# untitled.net
KiCad netlist of a schematic drawn in EAGLE
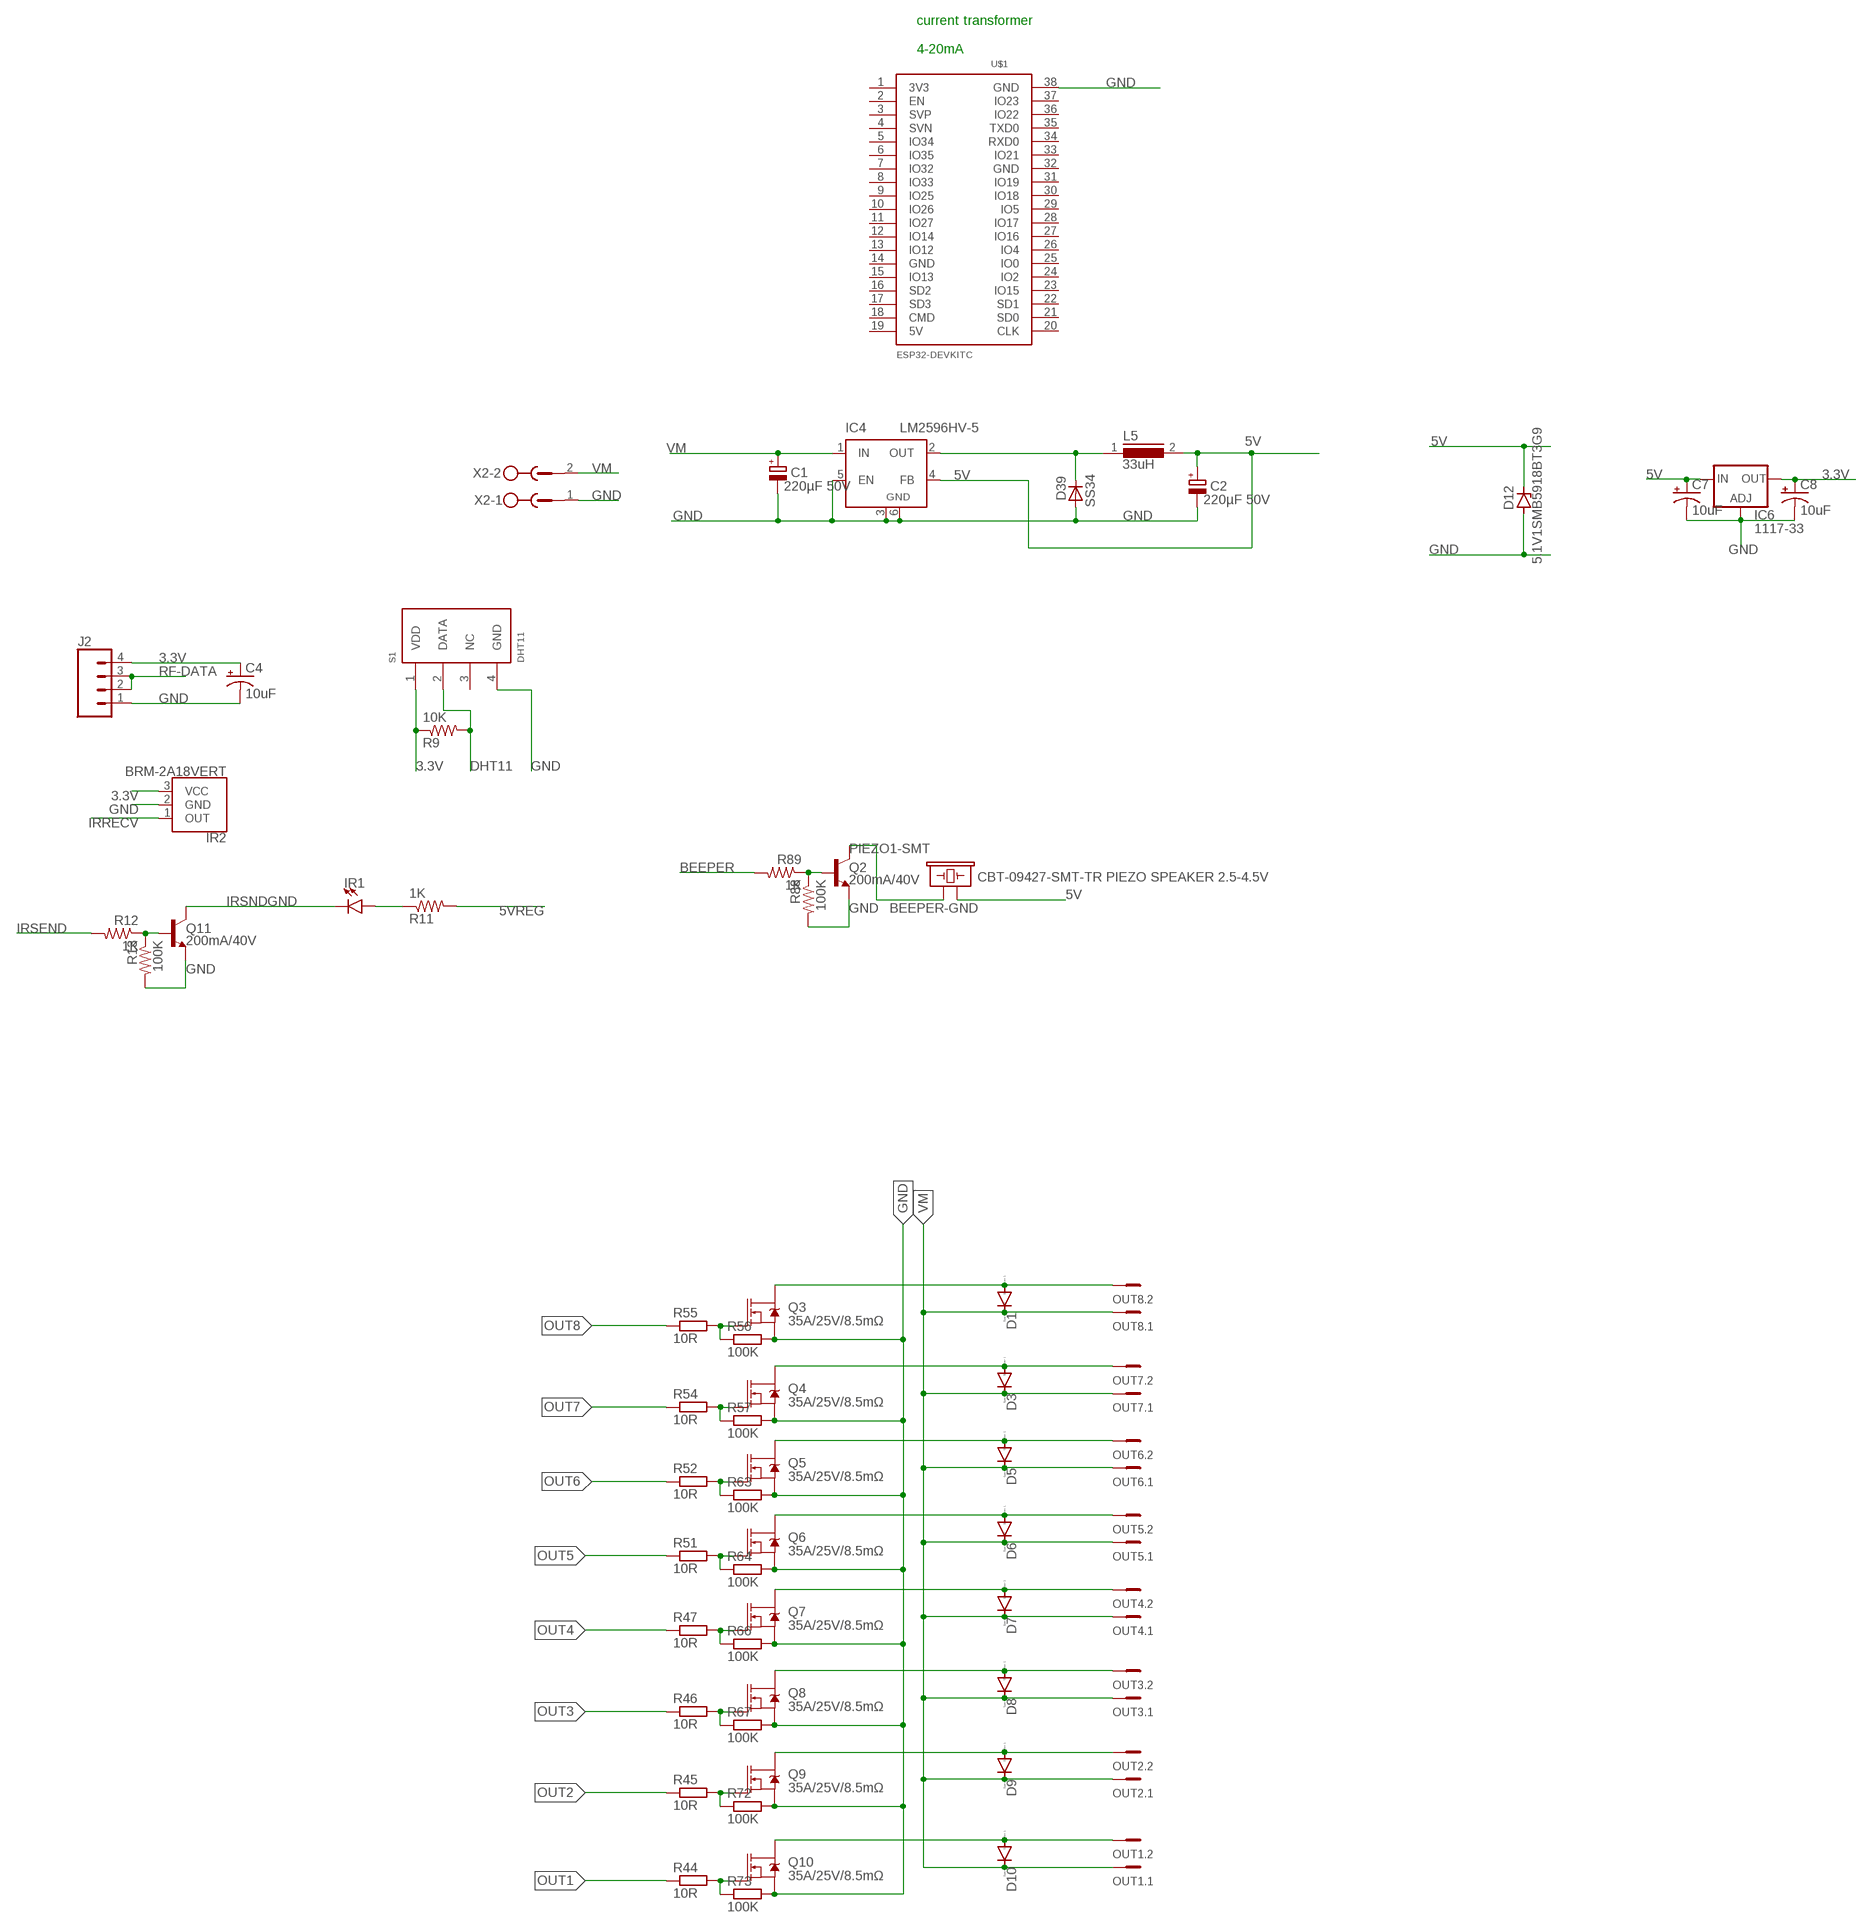
[diagram p0: schematic, sheet 1, part 1 of 2]
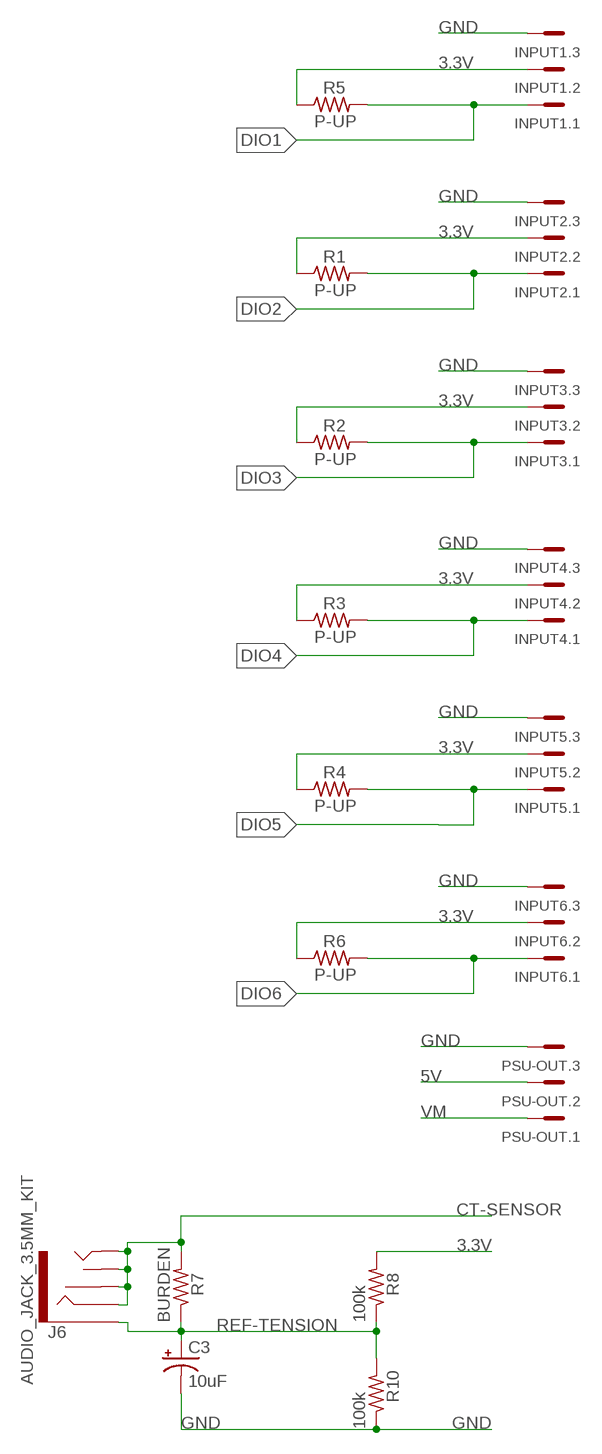
[diagram p1: schematic, sheet 1, part 2 of 2]

(export (version "E")
  (design (tool "Eeschema 10.0.6"))
  (components
    (comp (ref "C1")
      (value "220µF 50V")
      (footprint "eagle-import:E3,5-8")
      (libsource (lib "eagle-import") (part "CPOL-EUE3.5-8"))
    )
    (comp (ref "C2")
      (value "220µF 50V")
      (footprint "eagle-import:E3,5-8")
      (libsource (lib "eagle-import") (part "CPOL-EUE3.5-8"))
    )
    (comp (ref "C3")
      (value "10uF")
      (footprint "eagle-import:CPOL-RADIAL-10UF-25V")
      (libsource (lib "eagle-import") (part "CAP_POLPTH2"))
    )
    (comp (ref "C4")
      (value "10uF")
      (footprint "eagle-import:CPOL-RADIAL-10UF-25V")
      (libsource (lib "eagle-import") (part "CAP_POLPTH2"))
    )
    (comp (ref "C7")
      (value "10uF")
      (footprint "eagle-import:CPOL-RADIAL-10UF-25V")
      (libsource (lib "eagle-import") (part "CAP_POLPTH2"))
    )
    (comp (ref "C8")
      (value "10uF")
      (footprint "eagle-import:CPOL-RADIAL-10UF-25V")
      (libsource (lib "eagle-import") (part "CAP_POLPTH2"))
    )
    (comp (ref "D1")
      (value "1N4148DO35-7")
      (footprint "eagle-import:DO35-7")
      (libsource (lib "eagle-import") (part "1N4148DO35-7"))
    )
    (comp (ref "D3")
      (value "1N4148DO35-7")
      (footprint "eagle-import:DO35-7")
      (libsource (lib "eagle-import") (part "1N4148DO35-7"))
    )
    (comp (ref "D5")
      (value "1N4148DO35-7")
      (footprint "eagle-import:DO35-7")
      (libsource (lib "eagle-import") (part "1N4148DO35-7"))
    )
    (comp (ref "D6")
      (value "1N4148DO35-7")
      (footprint "eagle-import:DO35-7")
      (libsource (lib "eagle-import") (part "1N4148DO35-7"))
    )
    (comp (ref "D7")
      (value "1N4148DO35-7")
      (footprint "eagle-import:DO35-7")
      (libsource (lib "eagle-import") (part "1N4148DO35-7"))
    )
    (comp (ref "D8")
      (value "1N4148DO35-7")
      (footprint "eagle-import:DO35-7")
      (libsource (lib "eagle-import") (part "1N4148DO35-7"))
    )
    (comp (ref "D9")
      (value "1N4148DO35-7")
      (footprint "eagle-import:DO35-7")
      (libsource (lib "eagle-import") (part "1N4148DO35-7"))
    )
    (comp (ref "D10")
      (value "1N4148DO35-7")
      (footprint "eagle-import:DO35-7")
      (libsource (lib "eagle-import") (part "1N4148DO35-7"))
    )
    (comp (ref "D12")
      (value "5.1V1SMB5918BT3G9")
      (footprint "eagle-import:SMB")
      (libsource (lib "eagle-import") (part "ZENER-DIODESMB"))
    )
    (comp (ref "D39")
      (value "SS34")
      (footprint "eagle-import:SOD87")
      (libsource (lib "eagle-import") (part "D-SOD-87"))
    )
    (comp (ref "IC4")
      (value "LM2596HV-5")
      (footprint "eagle-import:TO263-5")
      (libsource (lib "eagle-import") (part "LM2596S"))
    )
    (comp (ref "IC6")
      (value "1117-33")
      (footprint "eagle-import:SOT223")
      (libsource (lib "eagle-import") (part "LD117A?S33TR"))
    )
    (comp (ref "INPUT1")
      (value "MCV3")
      (footprint "eagle-import:MCV3")
      (libsource (lib "eagle-import") (part "MCV3"))
    )
    (comp (ref "INPUT2")
      (value "MCV3")
      (footprint "eagle-import:MCV3")
      (libsource (lib "eagle-import") (part "MCV3"))
    )
    (comp (ref "INPUT3")
      (value "MCV3")
      (footprint "eagle-import:MCV3")
      (libsource (lib "eagle-import") (part "MCV3"))
    )
    (comp (ref "INPUT4")
      (value "MCV3")
      (footprint "eagle-import:MCV3")
      (libsource (lib "eagle-import") (part "MCV3"))
    )
    (comp (ref "INPUT5")
      (value "MCV3")
      (footprint "eagle-import:MCV3")
      (libsource (lib "eagle-import") (part "MCV3"))
    )
    (comp (ref "INPUT6")
      (value "MCV3")
      (footprint "eagle-import:MCV3")
      (libsource (lib "eagle-import") (part "MCV3"))
    )
    (comp (ref "IR1")
      (value "LED3MM")
      (footprint "eagle-import:LED_3MM")
      (libsource (lib "eagle-import") (part "LED3MM"))
    )
    (comp (ref "IR2")
      (value "BRM-2A18VERT")
      (footprint "eagle-import:BRM-2508_VERT")
      (libsource (lib "eagle-import") (part "BRM-2A18VERT"))
    )
    (comp (ref "J2")
      (value "CONN_04LOCK")
      (footprint "eagle-import:1X04_LOCK")
      (libsource (lib "eagle-import") (part "CONN_04LOCK"))
    )
    (comp (ref "J6")
      (value "AUDIO_JACK_3.5MM_KIT")
      (footprint "eagle-import:AUDIO-JACK-KIT")
      (libsource (lib "eagle-import") (part "AUDIO_JACK_3.5MM_KIT"))
    )
    (comp (ref "L5")
      (value "33uH")
      (footprint "eagle-import:DR127")
      (libsource (lib "eagle-import") (part "DR127"))
    )
    (comp (ref "OUT1")
      (value "MCV2")
      (footprint "eagle-import:MCV2")
      (libsource (lib "eagle-import") (part "MCV2"))
    )
    (comp (ref "OUT2")
      (value "MCV2")
      (footprint "eagle-import:MCV2")
      (libsource (lib "eagle-import") (part "MCV2"))
    )
    (comp (ref "OUT3")
      (value "MCV2")
      (footprint "eagle-import:MCV2")
      (libsource (lib "eagle-import") (part "MCV2"))
    )
    (comp (ref "OUT4")
      (value "MCV2")
      (footprint "eagle-import:MCV2")
      (libsource (lib "eagle-import") (part "MCV2"))
    )
    (comp (ref "OUT5")
      (value "MCV2")
      (footprint "eagle-import:MCV2")
      (libsource (lib "eagle-import") (part "MCV2"))
    )
    (comp (ref "OUT6")
      (value "MCV2")
      (footprint "eagle-import:MCV2")
      (libsource (lib "eagle-import") (part "MCV2"))
    )
    (comp (ref "OUT7")
      (value "MCV2")
      (footprint "eagle-import:MCV2")
      (libsource (lib "eagle-import") (part "MCV2"))
    )
    (comp (ref "OUT8")
      (value "MCV2")
      (footprint "eagle-import:MCV2")
      (libsource (lib "eagle-import") (part "MCV2"))
    )
    (comp (ref "PIEZO1-SMT")
      (value "CBT-09427-SMT-TR PIEZO SPEAKER 2.5-4.5V")
      (footprint "eagle-import:BUZZER-12MM")
      (libsource (lib "eagle-import") (part "BUZZER-PTH"))
    )
    (comp (ref "PSU-OUT")
      (value "MCV3")
      (footprint "eagle-import:MCV3")
      (libsource (lib "eagle-import") (part "MCV3"))
    )
    (comp (ref "Q2")
      (value "200mA/40V")
      (footprint "eagle-import:TO-92")
      (libsource (lib "eagle-import") (part "TRANS_NPN-2N3904"))
    )
    (comp (ref "Q3")
      (value "35A/25V/8.5mΩ")
      (footprint "eagle-import:DPAK")
      (libsource (lib "eagle-import") (part "MOSFET-NCH-FDD8780"))
    )
    (comp (ref "Q4")
      (value "35A/25V/8.5mΩ")
      (footprint "eagle-import:DPAK")
      (libsource (lib "eagle-import") (part "MOSFET-NCH-FDD8780"))
    )
    (comp (ref "Q5")
      (value "35A/25V/8.5mΩ")
      (footprint "eagle-import:DPAK")
      (libsource (lib "eagle-import") (part "MOSFET-NCH-FDD8780"))
    )
    (comp (ref "Q6")
      (value "35A/25V/8.5mΩ")
      (footprint "eagle-import:DPAK")
      (libsource (lib "eagle-import") (part "MOSFET-NCH-FDD8780"))
    )
    (comp (ref "Q7")
      (value "35A/25V/8.5mΩ")
      (footprint "eagle-import:DPAK")
      (libsource (lib "eagle-import") (part "MOSFET-NCH-FDD8780"))
    )
    (comp (ref "Q8")
      (value "35A/25V/8.5mΩ")
      (footprint "eagle-import:DPAK")
      (libsource (lib "eagle-import") (part "MOSFET-NCH-FDD8780"))
    )
    (comp (ref "Q9")
      (value "35A/25V/8.5mΩ")
      (footprint "eagle-import:DPAK")
      (libsource (lib "eagle-import") (part "MOSFET-NCH-FDD8780"))
    )
    (comp (ref "Q10")
      (value "35A/25V/8.5mΩ")
      (footprint "eagle-import:DPAK")
      (libsource (lib "eagle-import") (part "MOSFET-NCH-FDD8780"))
    )
    (comp (ref "Q11")
      (value "200mA/40V")
      (footprint "eagle-import:TO-92")
      (libsource (lib "eagle-import") (part "TRANS_NPN-2N3904"))
    )
    (comp (ref "R1")
      (value "P-UP")
      (footprint "eagle-import:0204_7")
      (libsource (lib "eagle-import") (part "resistor_R-US_0204/7"))
    )
    (comp (ref "R2")
      (value "P-UP")
      (footprint "eagle-import:0204_7")
      (libsource (lib "eagle-import") (part "resistor_R-US_0204/7"))
    )
    (comp (ref "R3")
      (value "P-UP")
      (footprint "eagle-import:0204_7")
      (libsource (lib "eagle-import") (part "resistor_R-US_0204/7"))
    )
    (comp (ref "R4")
      (value "P-UP")
      (footprint "eagle-import:0204_7")
      (libsource (lib "eagle-import") (part "resistor_R-US_0204/7"))
    )
    (comp (ref "R5")
      (value "P-UP")
      (footprint "eagle-import:0204_7")
      (libsource (lib "eagle-import") (part "resistor_R-US_0204/7"))
    )
    (comp (ref "R6")
      (value "P-UP")
      (footprint "eagle-import:0204_7")
      (libsource (lib "eagle-import") (part "resistor_R-US_0204/7"))
    )
    (comp (ref "R7")
      (value "BURDEN")
      (footprint "eagle-import:0204_7")
      (libsource (lib "eagle-import") (part "resistor_R-US_0204/7"))
    )
    (comp (ref "R8")
      (value "100k")
      (footprint "eagle-import:0204_7")
      (libsource (lib "eagle-import") (part "resistor_R-US_0204/7"))
    )
    (comp (ref "R9")
      (value "10K")
      (footprint "eagle-import:0204_7")
      (libsource (lib "eagle-import") (part "R-US_0204/7"))
    )
    (comp (ref "R10")
      (value "100k")
      (footprint "eagle-import:0204_7")
      (libsource (lib "eagle-import") (part "resistor_R-US_0204/7"))
    )
    (comp (ref "R11")
      (value "1K")
      (footprint "eagle-import:0204_7")
      (libsource (lib "eagle-import") (part "R-US_0204/7"))
    )
    (comp (ref "R12")
      (value "1K")
      (footprint "eagle-import:0204_7")
      (libsource (lib "eagle-import") (part "adafruit_420_R-US_0204/7"))
    )
    (comp (ref "R13")
      (value "100K")
      (footprint "eagle-import:0204_7")
      (libsource (lib "eagle-import") (part "adafruit_420_R-US_0204/7"))
    )
    (comp (ref "R44")
      (value "10R")
      (footprint "eagle-import:0204_7")
      (libsource (lib "eagle-import") (part "R-EU_0204/7"))
    )
    (comp (ref "R45")
      (value "10R")
      (footprint "eagle-import:0204_7")
      (libsource (lib "eagle-import") (part "R-EU_0204/7"))
    )
    (comp (ref "R46")
      (value "10R")
      (footprint "eagle-import:0204_7")
      (libsource (lib "eagle-import") (part "R-EU_0204/7"))
    )
    (comp (ref "R47")
      (value "10R")
      (footprint "eagle-import:0204_7")
      (libsource (lib "eagle-import") (part "R-EU_0204/7"))
    )
    (comp (ref "R51")
      (value "10R")
      (footprint "eagle-import:0204_7")
      (libsource (lib "eagle-import") (part "R-EU_0204/7"))
    )
    (comp (ref "R52")
      (value "10R")
      (footprint "eagle-import:0204_7")
      (libsource (lib "eagle-import") (part "R-EU_0204/7"))
    )
    (comp (ref "R54")
      (value "10R")
      (footprint "eagle-import:0204_7")
      (libsource (lib "eagle-import") (part "R-EU_0204/7"))
    )
    (comp (ref "R55")
      (value "10R")
      (footprint "eagle-import:0204_7")
      (libsource (lib "eagle-import") (part "R-EU_0204/7"))
    )
    (comp (ref "R56")
      (value "100K")
      (footprint "eagle-import:0204_7")
      (libsource (lib "eagle-import") (part "R-EU_0204/7"))
    )
    (comp (ref "R57")
      (value "100K")
      (footprint "eagle-import:0204_7")
      (libsource (lib "eagle-import") (part "R-EU_0204/7"))
    )
    (comp (ref "R63")
      (value "100K")
      (footprint "eagle-import:0204_7")
      (libsource (lib "eagle-import") (part "R-EU_0204/7"))
    )
    (comp (ref "R64")
      (value "100K")
      (footprint "eagle-import:0204_7")
      (libsource (lib "eagle-import") (part "R-EU_0204/7"))
    )
    (comp (ref "R66")
      (value "100K")
      (footprint "eagle-import:0204_7")
      (libsource (lib "eagle-import") (part "R-EU_0204/7"))
    )
    (comp (ref "R67")
      (value "100K")
      (footprint "eagle-import:0204_7")
      (libsource (lib "eagle-import") (part "R-EU_0204/7"))
    )
    (comp (ref "R72")
      (value "100K")
      (footprint "eagle-import:0204_7")
      (libsource (lib "eagle-import") (part "R-EU_0204/7"))
    )
    (comp (ref "R73")
      (value "100K")
      (footprint "eagle-import:0204_7")
      (libsource (lib "eagle-import") (part "R-EU_0204/7"))
    )
    (comp (ref "R88")
      (value "100K")
      (footprint "eagle-import:0204_7")
      (libsource (lib "eagle-import") (part "adafruit_420_R-US_0204/7"))
    )
    (comp (ref "R89")
      (value "1K")
      (footprint "eagle-import:0204_7")
      (libsource (lib "eagle-import") (part "adafruit_420_R-US_0204/7"))
    )
    (comp (ref "S1")
      (value "DHT11")
      (footprint "eagle-import:DHT11")
      (libsource (lib "eagle-import") (part "DHT11"))
    )
    (comp (ref "U$1")
      (value "ESP32NODEMCU")
      (footprint "eagle-import:ESP32NODEMCU")
      (libsource (lib "eagle-import") (part "ESP32NODEMCU"))
    )
    (comp (ref "X2")
      (value "MSTBV2")
      (footprint "eagle-import:MSTBV2")
      (libsource (lib "eagle-import") (part "MSTBV2"))
    )
  )
  (nets
    (net (code "1") (name "/3.3V") (class "Default")
      (node (ref "C4") (pin "1") (pinfunction "+_1") (pintype "passive"))
      (node (ref "C8") (pin "1") (pinfunction "+_1") (pintype "passive"))
      (node (ref "IC6") (pin "4") (pinfunction "OUT_4") (pintype "passive"))
      (node (ref "INPUT1") (pin "2") (pinfunction "SK_2") (pintype "passive"))
      (node (ref "INPUT2") (pin "2") (pinfunction "SK_2") (pintype "passive"))
      (node (ref "INPUT3") (pin "2") (pinfunction "SK_2") (pintype "passive"))
      (node (ref "INPUT4") (pin "2") (pinfunction "SK_2") (pintype "passive"))
      (node (ref "INPUT5") (pin "2") (pinfunction "SK_2") (pintype "passive"))
      (node (ref "INPUT6") (pin "2") (pinfunction "SK_2") (pintype "passive"))
      (node (ref "IR2") (pin "3") (pinfunction "VCC_3") (pintype "bidirectional"))
      (node (ref "J2") (pin "4") (pinfunction "4_4") (pintype "passive"))
      (node (ref "R1") (pin "1") (pinfunction "1_1") (pintype "passive"))
      (node (ref "R2") (pin "1") (pinfunction "1_1") (pintype "passive"))
      (node (ref "R3") (pin "1") (pinfunction "1_1") (pintype "passive"))
      (node (ref "R4") (pin "1") (pinfunction "1_1") (pintype "passive"))
      (node (ref "R5") (pin "1") (pinfunction "1_1") (pintype "passive"))
      (node (ref "R6") (pin "1") (pinfunction "1_1") (pintype "passive"))
      (node (ref "R8") (pin "2") (pinfunction "2_2") (pintype "passive"))
      (node (ref "R9") (pin "1") (pinfunction "1_1") (pintype "passive"))
      (node (ref "S1") (pin "1") (pinfunction "VDD_1") (pintype "power_in"))
    )
    (net (code "2") (name "/5V") (class "Default")
      (node (ref "C2") (pin "+") (pinfunction "+_+") (pintype "passive"))
      (node (ref "C7") (pin "1") (pinfunction "+_1") (pintype "passive"))
      (node (ref "D12") (pin "C") (pinfunction "C_C") (pintype "passive"))
      (node (ref "IC4") (pin "4") (pinfunction "FB_4") (pintype "input"))
      (node (ref "IC6") (pin "3") (pinfunction "IN_3") (pintype "input"))
      (node (ref "L5") (pin "2") (pinfunction "2_2") (pintype "passive"))
      (node (ref "PIEZO1-SMT") (pin "+") (pinfunction "1_+") (pintype "passive"))
      (node (ref "PSU-OUT") (pin "2") (pinfunction "SK_2") (pintype "passive"))
    )
    (net (code "3") (name "/5VREG") (class "Default")
      (node (ref "R11") (pin "2") (pinfunction "2_2") (pintype "passive"))
    )
    (net (code "4") (name "/BEEPER") (class "Default")
      (node (ref "R89") (pin "2") (pinfunction "2_2") (pintype "passive"))
    )
    (net (code "5") (name "/BEEPER-GND") (class "Default")
      (node (ref "PIEZO1-SMT") (pin "-") (pinfunction "2_-") (pintype "passive"))
      (node (ref "Q2") (pin "3") (pinfunction "C_3") (pintype "passive"))
    )
    (net (code "6") (name "/CT-SENSOR") (class "Default")
      (node (ref "J6") (pin "RING") (pinfunction "RING_RING") (pintype "bidirectional"))
      (node (ref "J6") (pin "RSH") (pinfunction "RSH_RSH") (pintype "bidirectional"))
      (node (ref "J6") (pin "TIP") (pinfunction "TIP_TIP") (pintype "bidirectional"))
      (node (ref "J6") (pin "TSH") (pinfunction "TSH_TSH") (pintype "bidirectional"))
      (node (ref "R7") (pin "2") (pinfunction "2_2") (pintype "passive"))
    )
    (net (code "7") (name "/DHT11") (class "Default")
      (node (ref "R9") (pin "2") (pinfunction "2_2") (pintype "passive"))
      (node (ref "S1") (pin "2") (pinfunction "DATA_2") (pintype "bidirectional"))
    )
    (net (code "8") (name "/IRRECV") (class "Default")
      (node (ref "IR2") (pin "1") (pinfunction "OUT_1") (pintype "bidirectional"))
    )
    (net (code "9") (name "/IRSEND") (class "Default")
      (node (ref "R12") (pin "2") (pinfunction "2_2") (pintype "passive"))
    )
    (net (code "10") (name "/IRSNDGND") (class "Default")
      (node (ref "IR1") (pin "K") (pinfunction "C_K") (pintype "passive"))
      (node (ref "Q11") (pin "3") (pinfunction "C_3") (pintype "passive"))
    )
    (net (code "11") (name "/REF-TENSION") (class "Default")
      (node (ref "C3") (pin "1") (pinfunction "+_1") (pintype "passive"))
      (node (ref "J6") (pin "SLEEVE") (pinfunction "SLEEVE_SLEEVE") (pintype "bidirectional"))
      (node (ref "R10") (pin "2") (pinfunction "2_2") (pintype "passive"))
      (node (ref "R7") (pin "1") (pinfunction "1_1") (pintype "passive"))
      (node (ref "R8") (pin "1") (pinfunction "1_1") (pintype "passive"))
    )
    (net (code "12") (name "/RF-DATA") (class "Default")
      (node (ref "J2") (pin "2") (pinfunction "2_2") (pintype "passive"))
      (node (ref "J2") (pin "3") (pinfunction "3_3") (pintype "passive"))
    )
    (net (code "13") (name "DIO1") (class "Default")
      (node (ref "INPUT1") (pin "1") (pinfunction "SK_1") (pintype "passive"))
      (node (ref "R5") (pin "2") (pinfunction "2_2") (pintype "passive"))
    )
    (net (code "14") (name "DIO2") (class "Default")
      (node (ref "INPUT2") (pin "1") (pinfunction "SK_1") (pintype "passive"))
      (node (ref "R1") (pin "2") (pinfunction "2_2") (pintype "passive"))
    )
    (net (code "15") (name "DIO3") (class "Default")
      (node (ref "INPUT3") (pin "1") (pinfunction "SK_1") (pintype "passive"))
      (node (ref "R2") (pin "2") (pinfunction "2_2") (pintype "passive"))
    )
    (net (code "16") (name "DIO4") (class "Default")
      (node (ref "INPUT4") (pin "1") (pinfunction "SK_1") (pintype "passive"))
      (node (ref "R3") (pin "2") (pinfunction "2_2") (pintype "passive"))
    )
    (net (code "17") (name "DIO5") (class "Default")
      (node (ref "INPUT5") (pin "1") (pinfunction "SK_1") (pintype "passive"))
      (node (ref "R4") (pin "2") (pinfunction "2_2") (pintype "passive"))
    )
    (net (code "18") (name "DIO6") (class "Default")
      (node (ref "INPUT6") (pin "1") (pinfunction "SK_1") (pintype "passive"))
      (node (ref "R6") (pin "2") (pinfunction "2_2") (pintype "passive"))
    )
    (net (code "19") (name "GND") (class "Default")
      (node (ref "C1") (pin "-") (pinfunction "-_-") (pintype "passive"))
      (node (ref "C2") (pin "-") (pinfunction "-_-") (pintype "passive"))
      (node (ref "C3") (pin "2") (pinfunction "-_2") (pintype "passive"))
      (node (ref "C4") (pin "2") (pinfunction "-_2") (pintype "passive"))
      (node (ref "C7") (pin "2") (pinfunction "-_2") (pintype "passive"))
      (node (ref "C8") (pin "2") (pinfunction "-_2") (pintype "passive"))
      (node (ref "D12") (pin "A") (pinfunction "A_A") (pintype "passive"))
      (node (ref "D39") (pin "2") (pinfunction "A_2") (pintype "passive"))
      (node (ref "IC4") (pin "3") (pinfunction "GND_3") (pintype "power_in"))
      (node (ref "IC4") (pin "5") (pinfunction "EN_5") (pintype "input"))
      (node (ref "IC4") (pin "6") (pinfunction "GND_6") (pintype "power_in"))
      (node (ref "IC6") (pin "1") (pinfunction "ADJ_1") (pintype "input"))
      (node (ref "INPUT1") (pin "3") (pinfunction "SK_3") (pintype "passive"))
      (node (ref "INPUT2") (pin "3") (pinfunction "SK_3") (pintype "passive"))
      (node (ref "INPUT3") (pin "3") (pinfunction "SK_3") (pintype "passive"))
      (node (ref "INPUT4") (pin "3") (pinfunction "SK_3") (pintype "passive"))
      (node (ref "INPUT5") (pin "3") (pinfunction "SK_3") (pintype "passive"))
      (node (ref "INPUT6") (pin "3") (pinfunction "SK_3") (pintype "passive"))
      (node (ref "IR2") (pin "2") (pinfunction "GND_2") (pintype "bidirectional"))
      (node (ref "J2") (pin "1") (pinfunction "1_1") (pintype "passive"))
      (node (ref "PSU-OUT") (pin "3") (pinfunction "SK_3") (pintype "passive"))
      (node (ref "Q10") (pin "3") (pinfunction "S_3") (pintype "bidirectional"))
      (node (ref "Q11") (pin "1") (pinfunction "E_1") (pintype "passive"))
      (node (ref "Q2") (pin "1") (pinfunction "E_1") (pintype "passive"))
      (node (ref "Q3") (pin "3") (pinfunction "S_3") (pintype "bidirectional"))
      (node (ref "Q4") (pin "3") (pinfunction "S_3") (pintype "bidirectional"))
      (node (ref "Q5") (pin "3") (pinfunction "S_3") (pintype "bidirectional"))
      (node (ref "Q6") (pin "3") (pinfunction "S_3") (pintype "bidirectional"))
      (node (ref "Q7") (pin "3") (pinfunction "S_3") (pintype "bidirectional"))
      (node (ref "Q8") (pin "3") (pinfunction "S_3") (pintype "bidirectional"))
      (node (ref "Q9") (pin "3") (pinfunction "S_3") (pintype "bidirectional"))
      (node (ref "R10") (pin "1") (pinfunction "1_1") (pintype "passive"))
      (node (ref "R13") (pin "2") (pinfunction "2_2") (pintype "passive"))
      (node (ref "R56") (pin "2") (pinfunction "2_2") (pintype "passive"))
      (node (ref "R57") (pin "2") (pinfunction "2_2") (pintype "passive"))
      (node (ref "R63") (pin "2") (pinfunction "2_2") (pintype "passive"))
      (node (ref "R64") (pin "2") (pinfunction "2_2") (pintype "passive"))
      (node (ref "R66") (pin "2") (pinfunction "2_2") (pintype "passive"))
      (node (ref "R67") (pin "2") (pinfunction "2_2") (pintype "passive"))
      (node (ref "R72") (pin "2") (pinfunction "2_2") (pintype "passive"))
      (node (ref "R73") (pin "2") (pinfunction "2_2") (pintype "passive"))
      (node (ref "R88") (pin "2") (pinfunction "2_2") (pintype "passive"))
      (node (ref "S1") (pin "4") (pinfunction "GND_4") (pintype "power_in"))
      (node (ref "U$1") (pin "38") (pinfunction "GND_38") (pintype "bidirectional"))
      (node (ref "X2") (pin "1") (pinfunction "SK_1") (pintype "passive"))
    )
    (net (code "20") (name "Net-(D39-C)") (class "Default")
      (node (ref "D39") (pin "1") (pinfunction "C_1") (pintype "passive"))
      (node (ref "IC4") (pin "2") (pinfunction "OUT_2") (pintype "output"))
      (node (ref "L5") (pin "1") (pinfunction "1_1") (pintype "passive"))
    )
    (net (code "21") (name "Net-(IR1-PadA)") (class "Default")
      (node (ref "IR1") (pin "A") (pinfunction "A_A") (pintype "passive"))
      (node (ref "R11") (pin "1") (pinfunction "1_1") (pintype "passive"))
    )
    (net (code "22") (name "Net-(OUT1B-SK)") (class "Default")
      (node (ref "D10") (pin "A") (pinfunction "A_A") (pintype "passive"))
      (node (ref "OUT1") (pin "2") (pinfunction "SK_2") (pintype "passive"))
      (node (ref "Q10") (pin "4") (pinfunction "D_4") (pintype "bidirectional"))
    )
    (net (code "23") (name "Net-(OUT2B-SK)") (class "Default")
      (node (ref "D9") (pin "A") (pinfunction "A_A") (pintype "passive"))
      (node (ref "OUT2") (pin "2") (pinfunction "SK_2") (pintype "passive"))
      (node (ref "Q9") (pin "4") (pinfunction "D_4") (pintype "bidirectional"))
    )
    (net (code "24") (name "Net-(OUT3B-SK)") (class "Default")
      (node (ref "D8") (pin "A") (pinfunction "A_A") (pintype "passive"))
      (node (ref "OUT3") (pin "2") (pinfunction "SK_2") (pintype "passive"))
      (node (ref "Q8") (pin "4") (pinfunction "D_4") (pintype "bidirectional"))
    )
    (net (code "25") (name "Net-(OUT4B-SK)") (class "Default")
      (node (ref "D7") (pin "A") (pinfunction "A_A") (pintype "passive"))
      (node (ref "OUT4") (pin "2") (pinfunction "SK_2") (pintype "passive"))
      (node (ref "Q7") (pin "4") (pinfunction "D_4") (pintype "bidirectional"))
    )
    (net (code "26") (name "Net-(OUT5B-SK)") (class "Default")
      (node (ref "D6") (pin "A") (pinfunction "A_A") (pintype "passive"))
      (node (ref "OUT5") (pin "2") (pinfunction "SK_2") (pintype "passive"))
      (node (ref "Q6") (pin "4") (pinfunction "D_4") (pintype "bidirectional"))
    )
    (net (code "27") (name "Net-(OUT6B-SK)") (class "Default")
      (node (ref "D5") (pin "A") (pinfunction "A_A") (pintype "passive"))
      (node (ref "OUT6") (pin "2") (pinfunction "SK_2") (pintype "passive"))
      (node (ref "Q5") (pin "4") (pinfunction "D_4") (pintype "bidirectional"))
    )
    (net (code "28") (name "Net-(OUT7B-SK)") (class "Default")
      (node (ref "D3") (pin "A") (pinfunction "A_A") (pintype "passive"))
      (node (ref "OUT7") (pin "2") (pinfunction "SK_2") (pintype "passive"))
      (node (ref "Q4") (pin "4") (pinfunction "D_4") (pintype "bidirectional"))
    )
    (net (code "29") (name "Net-(OUT8B-SK)") (class "Default")
      (node (ref "D1") (pin "A") (pinfunction "A_A") (pintype "passive"))
      (node (ref "OUT8") (pin "2") (pinfunction "SK_2") (pintype "passive"))
      (node (ref "Q3") (pin "4") (pinfunction "D_4") (pintype "bidirectional"))
    )
    (net (code "30") (name "Net-(Q2-B)") (class "Default")
      (node (ref "Q2") (pin "2") (pinfunction "B_2") (pintype "passive"))
      (node (ref "R88") (pin "1") (pinfunction "1_1") (pintype "passive"))
      (node (ref "R89") (pin "1") (pinfunction "1_1") (pintype "passive"))
    )
    (net (code "31") (name "Net-(Q3-G)") (class "Default")
      (node (ref "Q3") (pin "1") (pinfunction "G_1") (pintype "bidirectional"))
      (node (ref "R55") (pin "2") (pinfunction "2_2") (pintype "passive"))
      (node (ref "R56") (pin "1") (pinfunction "1_1") (pintype "passive"))
    )
    (net (code "32") (name "Net-(Q4-G)") (class "Default")
      (node (ref "Q4") (pin "1") (pinfunction "G_1") (pintype "bidirectional"))
      (node (ref "R54") (pin "2") (pinfunction "2_2") (pintype "passive"))
      (node (ref "R57") (pin "1") (pinfunction "1_1") (pintype "passive"))
    )
    (net (code "33") (name "Net-(Q5-G)") (class "Default")
      (node (ref "Q5") (pin "1") (pinfunction "G_1") (pintype "bidirectional"))
      (node (ref "R52") (pin "2") (pinfunction "2_2") (pintype "passive"))
      (node (ref "R63") (pin "1") (pinfunction "1_1") (pintype "passive"))
    )
    (net (code "34") (name "Net-(Q6-G)") (class "Default")
      (node (ref "Q6") (pin "1") (pinfunction "G_1") (pintype "bidirectional"))
      (node (ref "R51") (pin "2") (pinfunction "2_2") (pintype "passive"))
      (node (ref "R64") (pin "1") (pinfunction "1_1") (pintype "passive"))
    )
    (net (code "35") (name "Net-(Q7-G)") (class "Default")
      (node (ref "Q7") (pin "1") (pinfunction "G_1") (pintype "bidirectional"))
      (node (ref "R47") (pin "2") (pinfunction "2_2") (pintype "passive"))
      (node (ref "R66") (pin "1") (pinfunction "1_1") (pintype "passive"))
    )
    (net (code "36") (name "Net-(Q8-G)") (class "Default")
      (node (ref "Q8") (pin "1") (pinfunction "G_1") (pintype "bidirectional"))
      (node (ref "R46") (pin "2") (pinfunction "2_2") (pintype "passive"))
      (node (ref "R67") (pin "1") (pinfunction "1_1") (pintype "passive"))
    )
    (net (code "37") (name "Net-(Q9-G)") (class "Default")
      (node (ref "Q9") (pin "1") (pinfunction "G_1") (pintype "bidirectional"))
      (node (ref "R45") (pin "2") (pinfunction "2_2") (pintype "passive"))
      (node (ref "R72") (pin "1") (pinfunction "1_1") (pintype "passive"))
    )
    (net (code "38") (name "Net-(Q10-G)") (class "Default")
      (node (ref "Q10") (pin "1") (pinfunction "G_1") (pintype "bidirectional"))
      (node (ref "R44") (pin "2") (pinfunction "2_2") (pintype "passive"))
      (node (ref "R73") (pin "1") (pinfunction "1_1") (pintype "passive"))
    )
    (net (code "39") (name "Net-(Q11-B)") (class "Default")
      (node (ref "Q11") (pin "2") (pinfunction "B_2") (pintype "passive"))
      (node (ref "R12") (pin "1") (pinfunction "1_1") (pintype "passive"))
      (node (ref "R13") (pin "1") (pinfunction "1_1") (pintype "passive"))
    )
    (net (code "40") (name "OUT1") (class "Default")
      (node (ref "R44") (pin "1") (pinfunction "1_1") (pintype "passive"))
    )
    (net (code "41") (name "OUT2") (class "Default")
      (node (ref "R45") (pin "1") (pinfunction "1_1") (pintype "passive"))
    )
    (net (code "42") (name "OUT3") (class "Default")
      (node (ref "R46") (pin "1") (pinfunction "1_1") (pintype "passive"))
    )
    (net (code "43") (name "OUT4") (class "Default")
      (node (ref "R47") (pin "1") (pinfunction "1_1") (pintype "passive"))
    )
    (net (code "44") (name "OUT5") (class "Default")
      (node (ref "R51") (pin "1") (pinfunction "1_1") (pintype "passive"))
    )
    (net (code "45") (name "OUT6") (class "Default")
      (node (ref "R52") (pin "1") (pinfunction "1_1") (pintype "passive"))
    )
    (net (code "46") (name "OUT7") (class "Default")
      (node (ref "R54") (pin "1") (pinfunction "1_1") (pintype "passive"))
    )
    (net (code "47") (name "OUT8") (class "Default")
      (node (ref "R55") (pin "1") (pinfunction "1_1") (pintype "passive"))
    )
    (net (code "48") (name "VM") (class "Default")
      (node (ref "C1") (pin "+") (pinfunction "+_+") (pintype "passive"))
      (node (ref "D1") (pin "C") (pinfunction "C_C") (pintype "passive"))
      (node (ref "D10") (pin "C") (pinfunction "C_C") (pintype "passive"))
      (node (ref "D3") (pin "C") (pinfunction "C_C") (pintype "passive"))
      (node (ref "D5") (pin "C") (pinfunction "C_C") (pintype "passive"))
      (node (ref "D6") (pin "C") (pinfunction "C_C") (pintype "passive"))
      (node (ref "D7") (pin "C") (pinfunction "C_C") (pintype "passive"))
      (node (ref "D8") (pin "C") (pinfunction "C_C") (pintype "passive"))
      (node (ref "D9") (pin "C") (pinfunction "C_C") (pintype "passive"))
      (node (ref "IC4") (pin "1") (pinfunction "IN_1") (pintype "input"))
      (node (ref "OUT1") (pin "1") (pinfunction "SK_1") (pintype "passive"))
      (node (ref "OUT2") (pin "1") (pinfunction "SK_1") (pintype "passive"))
      (node (ref "OUT3") (pin "1") (pinfunction "SK_1") (pintype "passive"))
      (node (ref "OUT4") (pin "1") (pinfunction "SK_1") (pintype "passive"))
      (node (ref "OUT5") (pin "1") (pinfunction "SK_1") (pintype "passive"))
      (node (ref "OUT6") (pin "1") (pinfunction "SK_1") (pintype "passive"))
      (node (ref "OUT7") (pin "1") (pinfunction "SK_1") (pintype "passive"))
      (node (ref "OUT8") (pin "1") (pinfunction "SK_1") (pintype "passive"))
      (node (ref "PSU-OUT") (pin "1") (pinfunction "SK_1") (pintype "passive"))
      (node (ref "X2") (pin "2") (pinfunction "SK_2") (pintype "passive"))
    )
    (net (code "49") (name "unconnected-(S1-NC-Pad3)") (class "Default")
      (node (ref "S1") (pin "3") (pinfunction "NC_3") (pintype "bidirectional"))
    )
    (net (code "50") (name "unconnected-(U$1-3V3-Pad1)") (class "Default")
      (node (ref "U$1") (pin "1") (pinfunction "3V3_1") (pintype "bidirectional"))
    )
    (net (code "51") (name "unconnected-(U$1-5V-Pad19)") (class "Default")
      (node (ref "U$1") (pin "19") (pinfunction "5V_19") (pintype "bidirectional"))
    )
    (net (code "52") (name "unconnected-(U$1-CLK-Pad20)") (class "Default")
      (node (ref "U$1") (pin "20") (pinfunction "CLK_20") (pintype "bidirectional"))
    )
    (net (code "53") (name "unconnected-(U$1-CMD-Pad18)") (class "Default")
      (node (ref "U$1") (pin "18") (pinfunction "CMD_18") (pintype "bidirectional"))
    )
    (net (code "54") (name "unconnected-(U$1-EN-Pad2)") (class "Default")
      (node (ref "U$1") (pin "2") (pinfunction "EN_2") (pintype "bidirectional"))
    )
    (net (code "55") (name "unconnected-(U$1-GND-Pad14)") (class "Default")
      (node (ref "U$1") (pin "14") (pinfunction "GND_14") (pintype "bidirectional"))
    )
    (net (code "56") (name "unconnected-(U$1-GND-Pad32)") (class "Default")
      (node (ref "U$1") (pin "32") (pinfunction "GND_32") (pintype "bidirectional"))
    )
    (net (code "57") (name "unconnected-(U$1-IO0-Pad25)") (class "Default")
      (node (ref "U$1") (pin "25") (pinfunction "IO0_25") (pintype "bidirectional"))
    )
    (net (code "58") (name "unconnected-(U$1-IO2-Pad24)") (class "Default")
      (node (ref "U$1") (pin "24") (pinfunction "IO2_24") (pintype "bidirectional"))
    )
    (net (code "59") (name "unconnected-(U$1-IO4-Pad26)") (class "Default")
      (node (ref "U$1") (pin "26") (pinfunction "IO4_26") (pintype "bidirectional"))
    )
    (net (code "60") (name "unconnected-(U$1-IO5-Pad29)") (class "Default")
      (node (ref "U$1") (pin "29") (pinfunction "IO5_29") (pintype "bidirectional"))
    )
    (net (code "61") (name "unconnected-(U$1-IO12-Pad13)") (class "Default")
      (node (ref "U$1") (pin "13") (pinfunction "IO12_13") (pintype "bidirectional"))
    )
    (net (code "62") (name "unconnected-(U$1-IO13-Pad15)") (class "Default")
      (node (ref "U$1") (pin "15") (pinfunction "IO13_15") (pintype "bidirectional"))
    )
    (net (code "63") (name "unconnected-(U$1-IO14-Pad12)") (class "Default")
      (node (ref "U$1") (pin "12") (pinfunction "IO14_12") (pintype "bidirectional"))
    )
    (net (code "64") (name "unconnected-(U$1-IO15-Pad23)") (class "Default")
      (node (ref "U$1") (pin "23") (pinfunction "IO15_23") (pintype "bidirectional"))
    )
    (net (code "65") (name "unconnected-(U$1-IO16-Pad27)") (class "Default")
      (node (ref "U$1") (pin "27") (pinfunction "IO16_27") (pintype "bidirectional"))
    )
    (net (code "66") (name "unconnected-(U$1-IO17-Pad28)") (class "Default")
      (node (ref "U$1") (pin "28") (pinfunction "IO17_28") (pintype "bidirectional"))
    )
    (net (code "67") (name "unconnected-(U$1-IO18-Pad30)") (class "Default")
      (node (ref "U$1") (pin "30") (pinfunction "IO18_30") (pintype "bidirectional"))
    )
    (net (code "68") (name "unconnected-(U$1-IO19-Pad31)") (class "Default")
      (node (ref "U$1") (pin "31") (pinfunction "IO19_31") (pintype "bidirectional"))
    )
    (net (code "69") (name "unconnected-(U$1-IO21-Pad33)") (class "Default")
      (node (ref "U$1") (pin "33") (pinfunction "IO21_33") (pintype "bidirectional"))
    )
    (net (code "70") (name "unconnected-(U$1-IO22-Pad36)") (class "Default")
      (node (ref "U$1") (pin "36") (pinfunction "IO22_36") (pintype "bidirectional"))
    )
    (net (code "71") (name "unconnected-(U$1-IO23-Pad37)") (class "Default")
      (node (ref "U$1") (pin "37") (pinfunction "IO23_37") (pintype "bidirectional"))
    )
    (net (code "72") (name "unconnected-(U$1-IO25-Pad9)") (class "Default")
      (node (ref "U$1") (pin "9") (pinfunction "IO25_9") (pintype "bidirectional"))
    )
    (net (code "73") (name "unconnected-(U$1-IO26-Pad10)") (class "Default")
      (node (ref "U$1") (pin "10") (pinfunction "IO26_10") (pintype "bidirectional"))
    )
    (net (code "74") (name "unconnected-(U$1-IO27-Pad11)") (class "Default")
      (node (ref "U$1") (pin "11") (pinfunction "IO27_11") (pintype "bidirectional"))
    )
    (net (code "75") (name "unconnected-(U$1-IO32-Pad7)") (class "Default")
      (node (ref "U$1") (pin "7") (pinfunction "IO32_7") (pintype "bidirectional"))
    )
    (net (code "76") (name "unconnected-(U$1-IO33-Pad8)") (class "Default")
      (node (ref "U$1") (pin "8") (pinfunction "IO33_8") (pintype "bidirectional"))
    )
    (net (code "77") (name "unconnected-(U$1-IO34-Pad5)") (class "Default")
      (node (ref "U$1") (pin "5") (pinfunction "IO34_5") (pintype "bidirectional"))
    )
    (net (code "78") (name "unconnected-(U$1-IO35-Pad6)") (class "Default")
      (node (ref "U$1") (pin "6") (pinfunction "IO35_6") (pintype "bidirectional"))
    )
    (net (code "79") (name "unconnected-(U$1-RXD0-Pad34)") (class "Default")
      (node (ref "U$1") (pin "34") (pinfunction "RXD0_34") (pintype "bidirectional"))
    )
    (net (code "80") (name "unconnected-(U$1-SD0-Pad21)") (class "Default")
      (node (ref "U$1") (pin "21") (pinfunction "SD0_21") (pintype "bidirectional"))
    )
    (net (code "81") (name "unconnected-(U$1-SD1-Pad22)") (class "Default")
      (node (ref "U$1") (pin "22") (pinfunction "SD1_22") (pintype "bidirectional"))
    )
    (net (code "82") (name "unconnected-(U$1-SD2-Pad16)") (class "Default")
      (node (ref "U$1") (pin "16") (pinfunction "SD2_16") (pintype "bidirectional"))
    )
    (net (code "83") (name "unconnected-(U$1-SD3-Pad17)") (class "Default")
      (node (ref "U$1") (pin "17") (pinfunction "SD3_17") (pintype "bidirectional"))
    )
    (net (code "84") (name "unconnected-(U$1-SVN-Pad4)") (class "Default")
      (node (ref "U$1") (pin "4") (pinfunction "SVN_4") (pintype "bidirectional"))
    )
    (net (code "85") (name "unconnected-(U$1-SVP-Pad3)") (class "Default")
      (node (ref "U$1") (pin "3") (pinfunction "SVP_3") (pintype "bidirectional"))
    )
    (net (code "86") (name "unconnected-(U$1-TXD0-Pad35)") (class "Default")
      (node (ref "U$1") (pin "35") (pinfunction "TXD0_35") (pintype "bidirectional"))
    )
  )
)
